# Main.net
KiCad netlist of a schematic drawn in Altium Designer
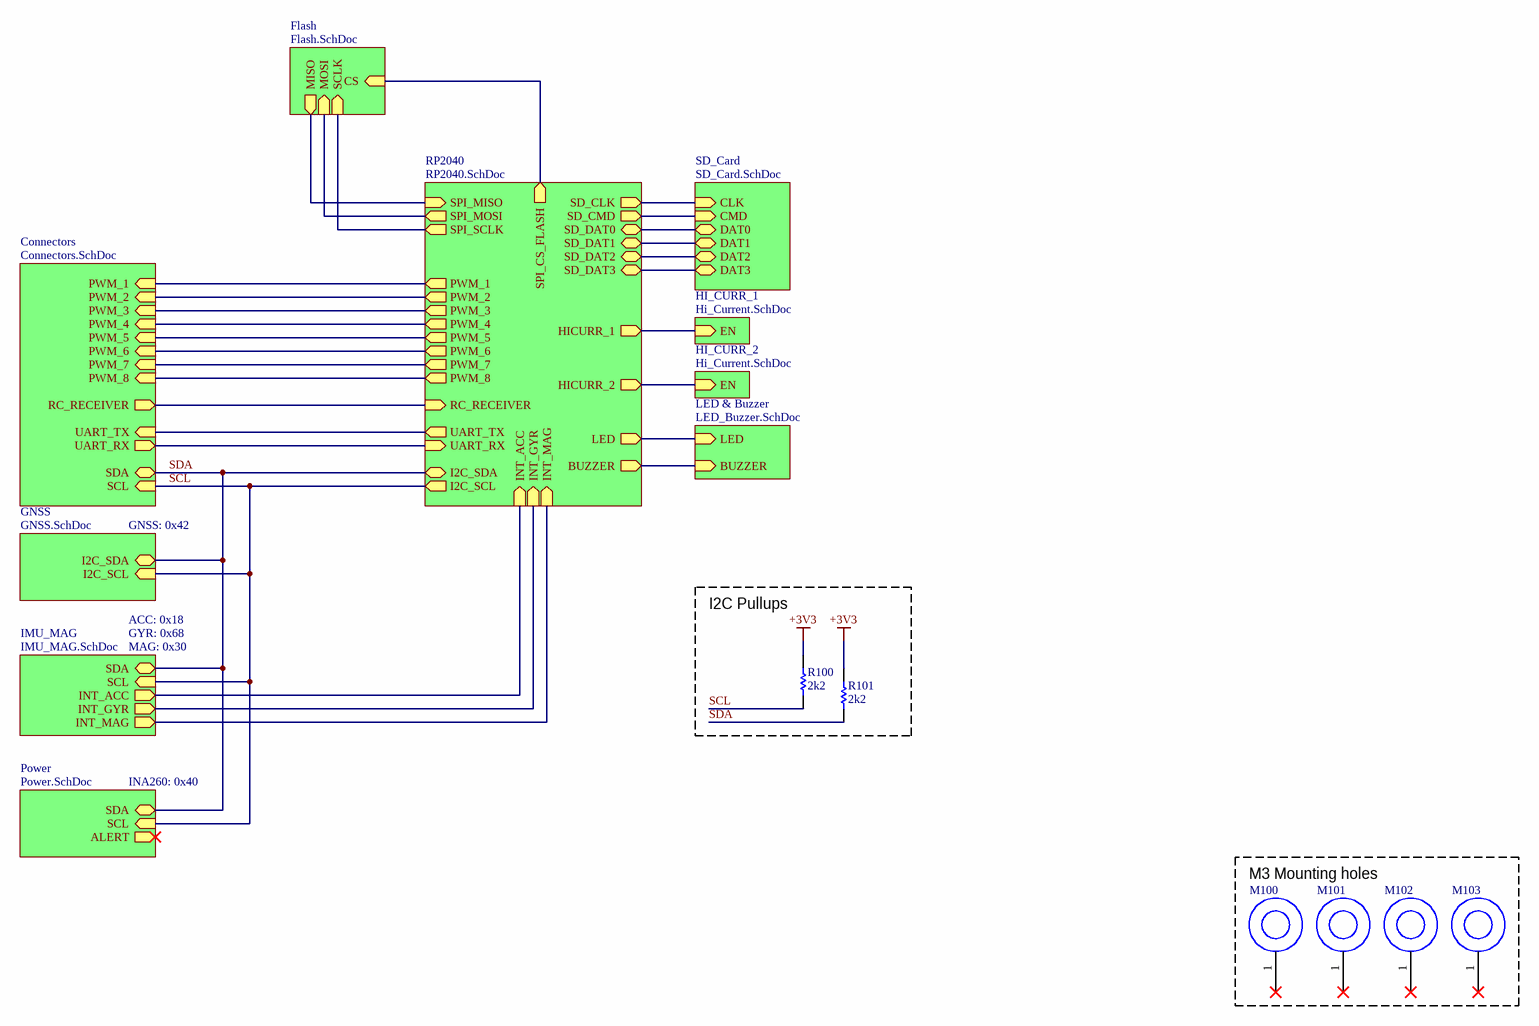
[diagram p0: Main.SchDoc]

(export (version "E")
  (design (tool "Eeschema 10.0.6"))
  (components
    (comp (ref "M100")
      (value "Mounting Screw")
      (footprint "M3_SCREW")
      (description "M4 and M3 scew holes, just pick the right footprint")
      (libsource (lib "Moonlight_Components") (part "Mounting Screw"))
    )
    (comp (ref "M101")
      (value "Mounting Screw")
      (footprint "M3_SCREW")
      (description "M4 and M3 scew holes, just pick the right footprint")
      (libsource (lib "Moonlight_Components") (part "Mounting Screw"))
    )
    (comp (ref "M102")
      (value "Mounting Screw")
      (footprint "M3_SCREW")
      (description "M4 and M3 scew holes, just pick the right footprint")
      (libsource (lib "Moonlight_Components") (part "Mounting Screw"))
    )
    (comp (ref "M103")
      (value "Mounting Screw")
      (footprint "M3_SCREW")
      (description "M4 and M3 scew holes, just pick the right footprint")
      (libsource (lib "Moonlight_Components") (part "Mounting Screw"))
    )
    (comp (ref "R100")
      (value "2k2")
      (footprint "0603_RES")
      (libsource (lib "Moonlight_Components") (part "Resistor"))
    )
    (comp (ref "R101")
      (value "2k2")
      (footprint "0603_RES")
      (libsource (lib "Moonlight_Components") (part "Resistor"))
    )
  )
  (nets
    (net (code "1") (name "+3V3") (class "Default")
      (node (ref "R100") (pin "1") (pinfunction "1_1") (pintype "passive"))
      (node (ref "R101") (pin "1") (pinfunction "1_1") (pintype "passive"))
    )
    (net (code "24") (name "/SCL") (class "Default")
      (node (ref "R100") (pin "2") (pinfunction "2_2") (pintype "passive"))
    )
    (net (code "25") (name "/SDA") (class "Default")
      (node (ref "R101") (pin "2") (pinfunction "2_2") (pintype "passive"))
    )
    (net (code "33") (name "unconnected-(M100-19-Pad1)") (class "Default")
      (node (ref "M100") (pin "1") (pinfunction "19_1") (pintype "passive+no_connect"))
    )
    (net (code "34") (name "unconnected-(M101-19-Pad1)") (class "Default")
      (node (ref "M101") (pin "1") (pinfunction "19_1") (pintype "passive+no_connect"))
    )
    (net (code "35") (name "unconnected-(M102-19-Pad1)") (class "Default")
      (node (ref "M102") (pin "1") (pinfunction "19_1") (pintype "passive+no_connect"))
    )
    (net (code "36") (name "unconnected-(M103-19-Pad1)") (class "Default")
      (node (ref "M103") (pin "1") (pinfunction "19_1") (pintype "passive+no_connect"))
    )
  )
)
